# Mikrokrmilnik_RF-detektor.net
KiCad netlist of a schematic drawn in Altium Designer
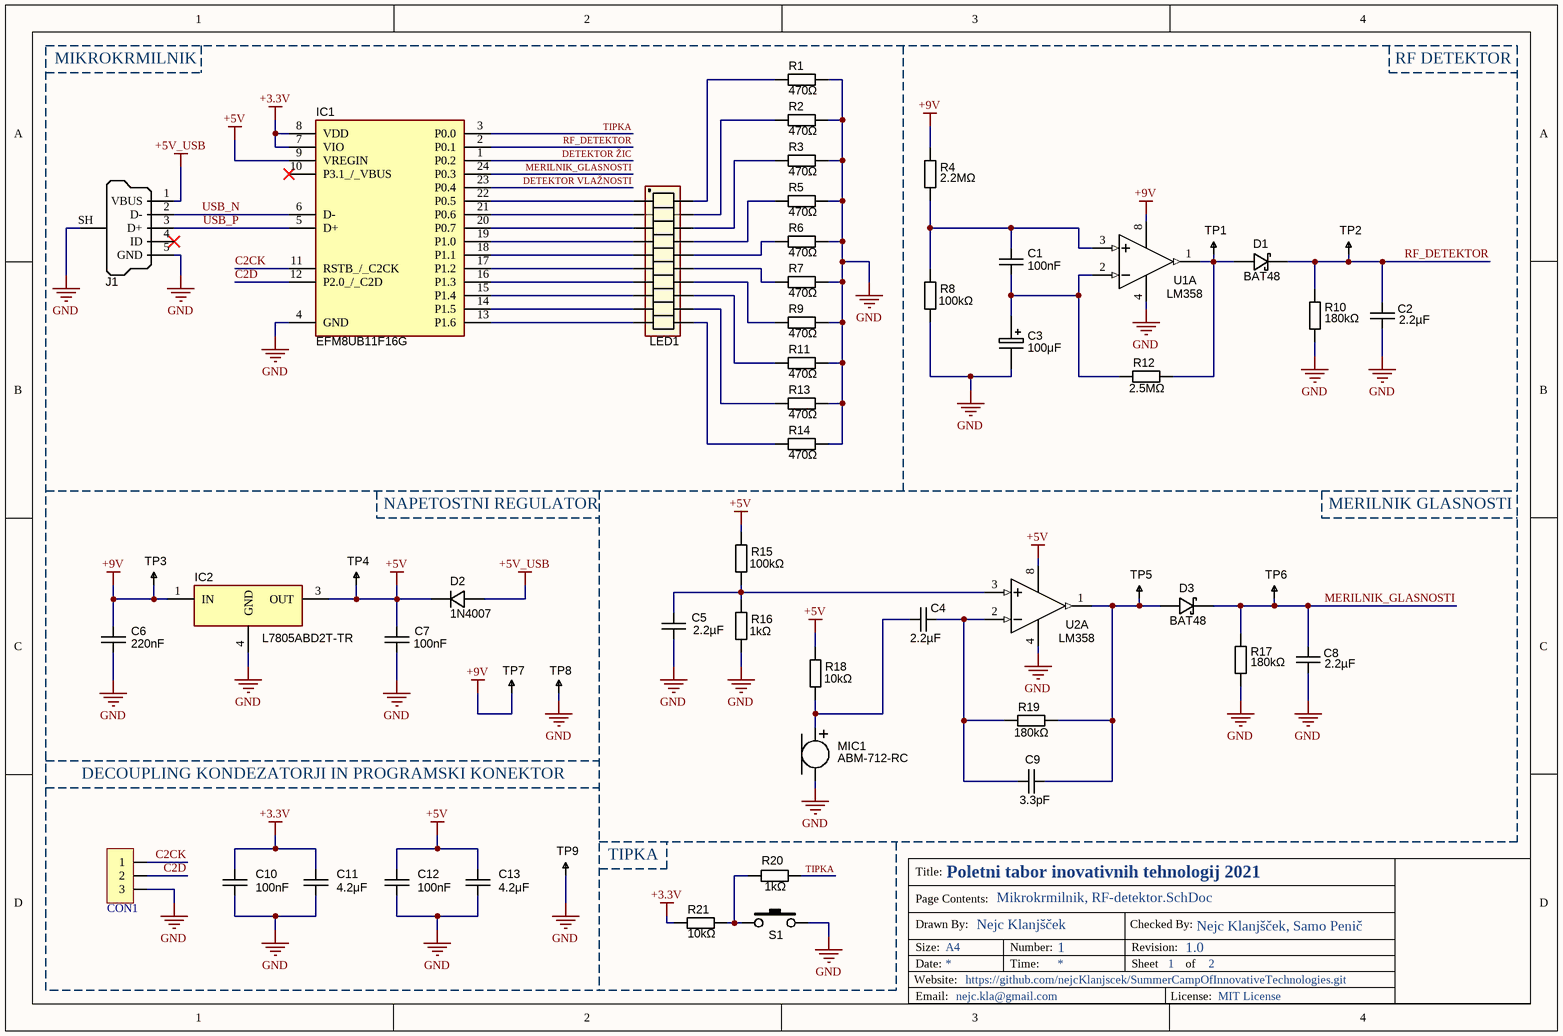
[diagram p0: Mikrokrmilnik, RF-detektor.SchDoc]

(export (version "E")
  (design (tool "Eeschema 10.0.6"))
  (components
    (comp (ref "C1")
      (value "100nF")
      (footprint "B32520C0104J000")
      (description "Capacitor THD Cer 100nF 10% 100V X7R B32520")
      (fields (field (name "TOLERANCE") "±10%") (field (name "Comment") "approved sub OK"))
      (libsource (lib "Nejc Klanjšček") (part "CAPC_220n_B32520"))
    )
    (comp (ref "C2")
      (value "2.2µF")
      (footprint "CAPC500P450250X550")
      (libsource (lib "Nejc Klanjšček") (part "CAPC_2u2_FG28_25V"))
    )
    (comp (ref "C3")
      (value "100μF")
      (footprint "CAPE_5x11x2LS")
      (libsource (lib "Nejc Klanjšček") (part "CAPT_10u_5mm_63V"))
    )
    (comp (ref "C4")
      (value "2.2µF")
      (footprint "CAPC500P450250X550")
      (libsource (lib "Nejc Klanjšček") (part "CAPC_2u2_FG28_25V"))
    )
    (comp (ref "C5")
      (value "2.2µF")
      (footprint "CAPC500P450250X550")
      (libsource (lib "Nejc Klanjšček") (part "CAPC_2u2_FG28_25V"))
    )
    (comp (ref "C6")
      (value "220nF")
      (footprint "CAPC3216N")
      (description "Capacitor SMD Cer 220nF 10% 10V X5R 1206")
      (fields (field (name "TOLERANCE") "±10%") (field (name "Comment") "approved sub OK"))
      (libsource (lib "Nejc Klanjšček") (part "CAPC_10u_1206_10V"))
    )
    (comp (ref "C7")
      (value "100nF")
      (footprint "CAPC3216N")
      (description "Capacitor SMD Cer 100nF 10% 10V X5R 1206")
      (fields (field (name "TOLERANCE") "±10%") (field (name "Comment") "approved sub OK"))
      (libsource (lib "Nejc Klanjšček") (part "CAPC_10u_1206_10V"))
    )
    (comp (ref "C8")
      (value "2.2µF")
      (footprint "CAPC500P450250X550")
      (libsource (lib "Nejc Klanjšček") (part "CAPC_2u2_FG28_25V"))
    )
    (comp (ref "C9")
      (value "3.3pF")
      (footprint "CAPC500P450250X550")
      (libsource (lib "Nejc Klanjšček") (part "CAPC_2u2_FG28_25V"))
    )
    (comp (ref "C10")
      (value "100nF")
      (footprint "CAPC3216N")
      (description "Capacitor SMD Cer 100nF 10% 10V X5R 1206")
      (fields (field (name "TOLERANCE") "±10%") (field (name "Comment") "approved sub OK"))
      (libsource (lib "Nejc Klanjšček") (part "CAPC_10u_1206_10V"))
    )
    (comp (ref "C11")
      (value "4.2μF")
      (footprint "CAPC3216N")
      (description "Capacitor SMD Cer 4.2uF 10% 10V X5R 1206")
      (fields (field (name "TOLERANCE") "±10%") (field (name "Comment") "approved sub OK"))
      (libsource (lib "Nejc Klanjšček") (part "CAPC_10u_1206_10V"))
    )
    (comp (ref "C12")
      (value "100nF")
      (footprint "CAPC3216N")
      (description "Capacitor SMD Cer 100nF 10% 10V X5R 1206")
      (fields (field (name "TOLERANCE") "±10%") (field (name "Comment") "approved sub OK"))
      (libsource (lib "Nejc Klanjšček") (part "CAPC_10u_1206_10V"))
    )
    (comp (ref "C13")
      (value "4.2μF")
      (footprint "CAPC3216N")
      (description "Capacitor SMD Cer 4.2uF 10% 10V X5R 1206")
      (fields (field (name "TOLERANCE") "±10%") (field (name "Comment") "approved sub OK"))
      (libsource (lib "Nejc Klanjšček") (part "CAPC_10u_1206_10V"))
    )
    (comp (ref "CON1")
      (value "H1x3")
      (footprint "H1x3")
      (description "Header 1x8 (male)")
      (libsource (lib "Nejc Klanjšček") (part "H1x3"))
    )
    (comp (ref "D1")
      (value "BAT48")
      (footprint "do-35")
      (description "Diode Schottky SMD 40V 350mA DO-35")
      (libsource (lib "Nejc Klanjšček") (part "DIODE_SCHOTTKY_BAT48"))
    )
    (comp (ref "D2")
      (value "1N4007")
      (footprint "DO-214AC")
      (description "Diode 1N4007 1A 1000V THD")
      (libsource (lib "Nejc Klanjšček") (part "DIODE_1N4007_1000V_1.0A_DO-41"))
    )
    (comp (ref "D3")
      (value "BAT48")
      (footprint "do-35")
      (description "Diode Schottky SMD 40V 350mA DO-35")
      (libsource (lib "Nejc Klanjšček") (part "DIODE_SCHOTTKY_BAT48"))
    )
    (comp (ref "IC1")
      (value "EFM8UB11F16G")
      (footprint "SOP64P600X175-24N")
      (description "Integrated Circuit")
      (fields
        (field (name "MANUFACTURER_PART_NUMBER") "EFM8UB11F16G-C-QSOP24")
        (field (name "MOUSER PART NUMBER") "634-8UB11F16GCQSOP24")
      )
      (libsource (lib "Nejc Klanjšček") (part "EFM8UB11F16G-C-QSOP24"))
    )
    (comp (ref "IC2")
      (value "L7805ABD2T-TR")
      (footprint "D2PAK-STB35NF10T4")
      (description "Integrated Circuit")
      (fields (field (name "MOUSER PART NUMBER") "511-L7805ABD2T-TR"))
      (libsource (lib "Nejc Klanjšček") (part "L7805ABD2T-TR"))
    )
    (comp (ref "J1")
      (value "USB Micro Type B")
      (footprint "USB_Micro-B_FCI_SMD")
      (description "Connector SMD-THD USB Micro Type B middle mount")
      (libsource (lib "Nejc Klanjšček") (part "USB_Micro_TypeB_FCI"))
    )
    (comp (ref "LED1")
      (value "SSA-LXB10HW-GF")
      (footprint "SSA-LXB10HW-GF")
      (libsource (lib "Nejc Klanjšček") (part "SSA-LXB10HW-GF"))
    )
    (comp (ref "MIC1")
      (value "ABM-712-RC")
      (footprint "ABM-707-RC")
      (libsource (lib "Nejc Klanjšček") (part "MICROPHONE_C_ABM-712-RC"))
    )
    (comp (ref "R1")
      (value "470Ω")
      (footprint "RESC3216N")
      (description "Resistor SMD chip 51 Ohm 0.25W 1% 1206")
      (fields (field (name "TOLERANCE") "±1%") (field (name "Comment") "Thick Film"))
      (libsource (lib "Nejc Klanjšček") (part "RES_51R_1206_1%"))
    )
    (comp (ref "R2")
      (value "470Ω")
      (footprint "RESC3216N")
      (description "Resistor SMD chip 51 Ohm 0.25W 1% 1206")
      (fields (field (name "TOLERANCE") "±1%") (field (name "Comment") "Thick Film"))
      (libsource (lib "Nejc Klanjšček") (part "RES_51R_1206_1%"))
    )
    (comp (ref "R3")
      (value "470Ω")
      (footprint "RESC3216N")
      (description "Resistor SMD chip 51 Ohm 0.25W 1% 1206")
      (fields (field (name "TOLERANCE") "±1%") (field (name "Comment") "Thick Film"))
      (libsource (lib "Nejc Klanjšček") (part "RES_51R_1206_1%"))
    )
    (comp (ref "R4")
      (value "2.2MΩ")
      (footprint "RESTH_AXIAL-1/8W")
      (description "Resistor THD Axial 2.2MΩ 0.125W 1% Carbon Film")
      (fields (field (name "TOLERANCE") "±5%") (field (name "Comment") "RES_NL_1/8W"))
      (libsource (lib "Nejc Klanjšček") (part "RES_NL_1/8W"))
    )
    (comp (ref "R5")
      (value "470Ω")
      (footprint "RESC3216N")
      (description "Resistor SMD chip 51 Ohm 0.25W 1% 1206")
      (fields (field (name "TOLERANCE") "±1%") (field (name "Comment") "Thick Film"))
      (libsource (lib "Nejc Klanjšček") (part "RES_51R_1206_1%"))
    )
    (comp (ref "R6")
      (value "470Ω")
      (footprint "RESC3216N")
      (description "Resistor SMD chip 51 Ohm 0.25W 1% 1206")
      (fields (field (name "TOLERANCE") "±1%") (field (name "Comment") "Thick Film"))
      (libsource (lib "Nejc Klanjšček") (part "RES_51R_1206_1%"))
    )
    (comp (ref "R7")
      (value "470Ω")
      (footprint "RESC3216N")
      (description "Resistor SMD chip 51 Ohm 0.25W 1% 1206")
      (fields (field (name "TOLERANCE") "±1%") (field (name "Comment") "Thick Film"))
      (libsource (lib "Nejc Klanjšček") (part "RES_51R_1206_1%"))
    )
    (comp (ref "R8")
      (value "100kΩ")
      (footprint "RESTH_AXIAL-1/8W")
      (description "Resistor THD Axial 100kΩ 0.125W 1% Carbon Film")
      (fields (field (name "TOLERANCE") "±5%") (field (name "Comment") "RES_NL_1/8W"))
      (libsource (lib "Nejc Klanjšček") (part "RES_NL_1/8W"))
    )
    (comp (ref "R9")
      (value "470Ω")
      (footprint "RESC3216N")
      (description "Resistor SMD chip 51 Ohm 0.25W 1% 1206")
      (fields (field (name "TOLERANCE") "±1%") (field (name "Comment") "Thick Film"))
      (libsource (lib "Nejc Klanjšček") (part "RES_51R_1206_1%"))
    )
    (comp (ref "R10")
      (value "180kΩ")
      (footprint "RESTH_AXIAL-1/8W")
      (description "Resistor THD Axial 180kΩ 0.125W 1% Carbon Film")
      (fields (field (name "TOLERANCE") "±5%") (field (name "Comment") "RES_NL_1/8W"))
      (libsource (lib "") (part "RES_NL_1/8W_1"))
    )
    (comp (ref "R11")
      (value "470Ω")
      (footprint "RESC3216N")
      (description "Resistor SMD chip 51 Ohm 0.25W 1% 1206")
      (fields (field (name "TOLERANCE") "±1%") (field (name "Comment") "Thick Film"))
      (libsource (lib "Nejc Klanjšček") (part "RES_51R_1206_1%"))
    )
    (comp (ref "R12")
      (value "2.5MΩ")
      (footprint "RESTH_AXIAL-1/8W")
      (description "Resistor THD Axial 2.5MΩ 0.125W 1% Carbon Film")
      (fields (field (name "TOLERANCE") "±5%") (field (name "Comment") "RES_NL_1/8W"))
      (libsource (lib "") (part "RES_NL_1/8W_2"))
    )
    (comp (ref "R13")
      (value "470Ω")
      (footprint "RESC3216N")
      (description "Resistor SMD chip 51 Ohm 0.25W 1% 1206")
      (fields (field (name "TOLERANCE") "±1%") (field (name "Comment") "Thick Film"))
      (libsource (lib "Nejc Klanjšček") (part "RES_51R_1206_1%"))
    )
    (comp (ref "R14")
      (value "470Ω")
      (footprint "RESC3216N")
      (description "Resistor SMD chip 51 Ohm 0.25W 1% 1206")
      (fields (field (name "TOLERANCE") "±1%") (field (name "Comment") "Thick Film"))
      (libsource (lib "Nejc Klanjšček") (part "RES_51R_1206_1%"))
    )
    (comp (ref "R15")
      (value "100kΩ")
      (footprint "RESTH_AXIAL-1/8W")
      (description "Resistor THD Axial 100kΩ 0.125W 1% Carbon Film")
      (fields (field (name "TOLERANCE") "±5%") (field (name "Comment") "RES_NL_1/8W"))
      (libsource (lib "Nejc Klanjšček") (part "RES_NL_1/8W"))
    )
    (comp (ref "R16")
      (value "1kΩ")
      (footprint "RESTH_AXIAL-1/8W")
      (description "Resistor THD Axial 1kΩ 0.125W 1% Carbon Film")
      (fields (field (name "TOLERANCE") "±5%") (field (name "Comment") "RES_NL_1/8W"))
      (libsource (lib "Nejc Klanjšček") (part "RES_NL_1/8W"))
    )
    (comp (ref "R17")
      (value "180kΩ")
      (footprint "RESTH_AXIAL-1/8W")
      (description "Resistor THD Axial 180kΩ 0.125W 1% Carbon Film")
      (fields (field (name "TOLERANCE") "±5%") (field (name "Comment") "RES_NL_1/8W"))
      (libsource (lib "") (part "RES_NL_1/8W_1"))
    )
    (comp (ref "R18")
      (value "10kΩ")
      (footprint "RESTH_AXIAL-1/8W")
      (description "Resistor THD Axial 1kΩ 0.125W 1% Carbon Film")
      (fields (field (name "TOLERANCE") "±5%") (field (name "Comment") "RES_NL_1/8W"))
      (libsource (lib "Nejc Klanjšček") (part "RES_NL_1/8W"))
    )
    (comp (ref "R19")
      (value "180kΩ")
      (footprint "RESTH_AXIAL-1/8W")
      (description "Resistor THD Axial 180kΩ 0.125W 1% Carbon Film")
      (fields (field (name "TOLERANCE") "±5%") (field (name "Comment") "RES_NL_1/8W"))
      (libsource (lib "") (part "RES_NL_1/8W_3"))
    )
    (comp (ref "R20")
      (value "1kΩ")
      (footprint "RESC3216N")
      (description "Resistor SMD chip 1k Ohm 0.25W 1% 1206")
      (fields (field (name "TOLERANCE") "±1%") (field (name "Comment") "Thick Film"))
      (libsource (lib "Nejc Klanjšček") (part "RES_51R_1206_1%"))
    )
    (comp (ref "R21")
      (value "10kΩ")
      (footprint "RESC3216N")
      (description "Resistor SMD chip 10k Ohm 0.25W 1% 1206")
      (fields (field (name "TOLERANCE") "±1%") (field (name "Comment") "Thick Film"))
      (libsource (lib "") (part "RES_51R_1206_1%_1"))
    )
    (comp (ref "S1")
      (value "SW_THT_PB_7.0mm")
      (footprint "TACT-SWITCH-TS1170")
      (description "Switch, tact, 7.0mm stem")
      (libsource (lib "Nejc Klanjšček") (part "SW_THT_PB_7.0mm"))
    )
    (comp (ref "TP1")
      (value "TESTPOINT")
      (footprint "TP-R60")
      (description "SMD test pin")
      (libsource (lib "Nejc Klanjšček") (part "TESTPOINT"))
    )
    (comp (ref "TP2")
      (value "TESTPOINT")
      (footprint "TP-R60")
      (description "SMD test pin")
      (libsource (lib "Nejc Klanjšček") (part "TESTPOINT"))
    )
    (comp (ref "TP3")
      (value "TESTPOINT")
      (footprint "TP-R60")
      (description "SMD test pin")
      (libsource (lib "Nejc Klanjšček") (part "TESTPOINT"))
    )
    (comp (ref "TP4")
      (value "TESTPOINT")
      (footprint "TP-R60")
      (description "SMD test pin")
      (libsource (lib "Nejc Klanjšček") (part "TESTPOINT"))
    )
    (comp (ref "TP5")
      (value "TESTPOINT")
      (footprint "TP-R60")
      (description "SMD test pin")
      (libsource (lib "Nejc Klanjšček") (part "TESTPOINT"))
    )
    (comp (ref "TP6")
      (value "TESTPOINT")
      (footprint "TP-R60")
      (description "SMD test pin")
      (libsource (lib "Nejc Klanjšček") (part "TESTPOINT"))
    )
    (comp (ref "TP7")
      (value "TESTPOINT_THT")
      (footprint "TP-THT-MULTI")
      (description "Test Point PCB mount Multi-purpose Yellow")
      (libsource (lib "Nejc Klanjšček") (part "TESTPOINT_THT"))
    )
    (comp (ref "TP8")
      (value "TESTPOINT_THT")
      (footprint "TP-THT-MULTI")
      (description "Test Point PCB mount Multi-purpose Yellow")
      (libsource (lib "Nejc Klanjšček") (part "TESTPOINT_THT"))
    )
    (comp (ref "TP9")
      (value "TESTPOINT")
      (footprint "TP-R60")
      (description "SMD test pin")
      (libsource (lib "Nejc Klanjšček") (part "TESTPOINT"))
    )
    (comp (ref "U1")
      (value "LM358")
      (footprint "DIP8-300")
      (description "IC THD Op Amp Precision Micropower SOIC-8")
      (libsource (lib "Nejc Klanjšček") (part "IC_Op-Amp_LM358"))
    )
    (comp (ref "U2")
      (value "LM358")
      (footprint "DIP8-300")
      (description "IC THD Op Amp Precision Micropower SOIC-8")
      (libsource (lib "Nejc Klanjšček") (part "IC_Op-Amp_LM358"))
    )
  )
  (nets
    (net (code "1") (name "+3.3V") (class "Default")
      (node (ref "C10") (pin "1") (pintype "passive"))
      (node (ref "C11") (pin "1") (pintype "passive"))
      (node (ref "IC1") (pin "7") (pinfunction "VIO_7") (pintype "passive"))
      (node (ref "IC1") (pin "8") (pinfunction "VDD_8") (pintype "passive"))
      (node (ref "R21") (pin "1") (pinfunction "1_1") (pintype "passive"))
    )
    (net (code "2") (name "+5V") (class "Default")
      (node (ref "C12") (pin "1") (pintype "passive"))
      (node (ref "C13") (pin "1") (pintype "passive"))
      (node (ref "C7") (pin "1") (pintype "passive"))
      (node (ref "D2") (pin "K") (pinfunction "K_K") (pintype "passive"))
      (node (ref "IC1") (pin "9") (pinfunction "VREGIN_9") (pintype "passive"))
      (node (ref "IC2") (pin "3") (pinfunction "OUT_3") (pintype "passive"))
      (node (ref "R15") (pin "1") (pinfunction "1_1") (pintype "passive"))
      (node (ref "R18") (pin "1") (pinfunction "1_1") (pintype "passive"))
      (node (ref "TP4") (pin "1") (pintype "passive"))
      (node (ref "U2") (pin "8") (pinfunction "V+_8") (pintype "power_in"))
    )
    (net (code "3") (name "+5V_USB") (class "Default")
      (node (ref "D2") (pin "A") (pinfunction "A_A") (pintype "passive"))
      (node (ref "J1") (pin "1") (pinfunction "VBUS_1") (pintype "passive"))
    )
    (net (code "4") (name "+9V") (class "Default")
      (node (ref "C6") (pin "1") (pintype "passive"))
      (node (ref "IC2") (pin "1") (pinfunction "IN_1") (pintype "passive"))
      (node (ref "R4") (pin "1") (pinfunction "1_1") (pintype "passive"))
      (node (ref "TP3") (pin "1") (pintype "passive"))
      (node (ref "TP7") (pin "1") (pintype "passive"))
      (node (ref "U1") (pin "8") (pinfunction "V+_8") (pintype "power_in"))
    )
    (net (code "5") (name "/C2CK") (class "Default")
      (node (ref "CON1") (pin "1") (pinfunction "1_1") (pintype "passive"))
      (node (ref "IC1") (pin "11") (pinfunction "RSTB_/_C2CK_11") (pintype "passive"))
    )
    (net (code "6") (name "/C2D") (class "Default")
      (node (ref "CON1") (pin "2") (pinfunction "2_2") (pintype "passive"))
      (node (ref "IC1") (pin "12") (pinfunction "P2.0_/_C2D_12") (pintype "passive"))
    )
    (net (code "7") (name "/DETEKTOR VLAŽNOSTI") (class "Default")
      (node (ref "IC1") (pin "23") (pinfunction "P0.4_23") (pintype "passive"))
    )
    (net (code "8") (name "/DETEKTOR ŽIC") (class "Default")
      (node (ref "IC1") (pin "1") (pinfunction "P0.2_1") (pintype "passive"))
    )
    (net (code "9") (name "/MERILNIK_GLASNOSTI") (class "Default")
      (node (ref "C8") (pin "1") (pintype "passive"))
      (node (ref "D3") (pin "K") (pinfunction "K_K") (pintype "passive"))
      (node (ref "IC1") (pin "24") (pinfunction "P0.3_24") (pintype "passive"))
      (node (ref "R17") (pin "2") (pinfunction "2_2") (pintype "passive"))
      (node (ref "TP6") (pin "1") (pintype "passive"))
    )
    (net (code "10") (name "/RF_DETEKTOR") (class "Default")
      (node (ref "C2") (pin "1") (pintype "passive"))
      (node (ref "D1") (pin "K") (pinfunction "K_K") (pintype "passive"))
      (node (ref "IC1") (pin "2") (pinfunction "P0.1_2") (pintype "passive"))
      (node (ref "R10") (pin "2") (pinfunction "2_2") (pintype "passive"))
      (node (ref "TP2") (pin "1") (pintype "passive"))
    )
    (net (code "11") (name "/TIPKA") (class "Default")
      (node (ref "IC1") (pin "3") (pinfunction "P0.0_3") (pintype "passive"))
      (node (ref "R20") (pin "1") (pinfunction "1_1") (pintype "passive"))
    )
    (net (code "12") (name "/USB_N") (class "Default")
      (node (ref "IC1") (pin "6") (pinfunction "D-_6") (pintype "passive"))
      (node (ref "J1") (pin "2") (pinfunction "D-_2") (pintype "passive"))
    )
    (net (code "13") (name "/USB_P") (class "Default")
      (node (ref "IC1") (pin "5") (pinfunction "D+_5") (pintype "passive"))
      (node (ref "J1") (pin "3") (pinfunction "D+_3") (pintype "passive"))
    )
    (net (code "14") (name "GND") (class "Default")
      (node (ref "C10") (pin "2") (pintype "passive"))
      (node (ref "C11") (pin "2") (pintype "passive"))
      (node (ref "C12") (pin "2") (pintype "passive"))
      (node (ref "C13") (pin "2") (pintype "passive"))
      (node (ref "C2") (pin "2") (pintype "passive"))
      (node (ref "C3") (pin "2") (pintype "passive"))
      (node (ref "C5") (pin "1") (pintype "passive"))
      (node (ref "C6") (pin "2") (pintype "passive"))
      (node (ref "C7") (pin "2") (pintype "passive"))
      (node (ref "C8") (pin "2") (pintype "passive"))
      (node (ref "CON1") (pin "3") (pinfunction "3_3") (pintype "passive"))
      (node (ref "IC1") (pin "4") (pinfunction "GND_4") (pintype "passive"))
      (node (ref "IC2") (pin "4") (pinfunction "GND_4") (pintype "passive"))
      (node (ref "J1") (pin "5") (pinfunction "GND_5") (pintype "passive"))
      (node (ref "J1") (pin "SH") (pinfunction "Shell_SH") (pintype "passive"))
      (node (ref "MIC1") (pin "2") (pinfunction "-_2") (pintype "passive"))
      (node (ref "R1") (pin "1") (pinfunction "1_1") (pintype "passive"))
      (node (ref "R10") (pin "1") (pinfunction "1_1") (pintype "passive"))
      (node (ref "R11") (pin "1") (pinfunction "1_1") (pintype "passive"))
      (node (ref "R13") (pin "1") (pinfunction "1_1") (pintype "passive"))
      (node (ref "R14") (pin "1") (pinfunction "1_1") (pintype "passive"))
      (node (ref "R16") (pin "2") (pinfunction "2_2") (pintype "passive"))
      (node (ref "R17") (pin "1") (pinfunction "1_1") (pintype "passive"))
      (node (ref "R2") (pin "1") (pinfunction "1_1") (pintype "passive"))
      (node (ref "R3") (pin "1") (pinfunction "1_1") (pintype "passive"))
      (node (ref "R5") (pin "1") (pinfunction "1_1") (pintype "passive"))
      (node (ref "R6") (pin "1") (pinfunction "1_1") (pintype "passive"))
      (node (ref "R7") (pin "1") (pinfunction "1_1") (pintype "passive"))
      (node (ref "R8") (pin "2") (pinfunction "2_2") (pintype "passive"))
      (node (ref "R9") (pin "1") (pinfunction "1_1") (pintype "passive"))
      (node (ref "S1") (pin "2") (pintype "passive"))
      (node (ref "TP8") (pin "1") (pintype "passive"))
      (node (ref "TP9") (pin "1") (pintype "passive"))
      (node (ref "U1") (pin "4") (pinfunction "V-_4") (pintype "power_in"))
      (node (ref "U2") (pin "4") (pinfunction "V-_4") (pintype "power_in"))
    )
    (net (code "15") (name "Net-(IC1-P0.5)") (class "Default")
      (node (ref "IC1") (pin "22") (pinfunction "P0.5_22") (pintype "passive"))
      (node (ref "LED1") (pin "1") (pinfunction "1_1") (pintype "passive"))
    )
    (net (code "16") (name "Net-(IC1-P0.6)") (class "Default")
      (node (ref "IC1") (pin "21") (pinfunction "P0.6_21") (pintype "passive"))
      (node (ref "LED1") (pin "2") (pinfunction "2_2") (pintype "passive"))
    )
    (net (code "17") (name "Net-(IC1-P0.7)") (class "Default")
      (node (ref "IC1") (pin "20") (pinfunction "P0.7_20") (pintype "passive"))
      (node (ref "LED1") (pin "3") (pinfunction "3_3") (pintype "passive"))
    )
    (net (code "18") (name "Net-(IC1-P1.0)") (class "Default")
      (node (ref "IC1") (pin "19") (pinfunction "P1.0_19") (pintype "passive"))
      (node (ref "LED1") (pin "4") (pinfunction "4_4") (pintype "passive"))
    )
    (net (code "19") (name "Net-(IC1-P1.1)") (class "Default")
      (node (ref "IC1") (pin "18") (pinfunction "P1.1_18") (pintype "passive"))
      (node (ref "LED1") (pin "5") (pinfunction "5_5") (pintype "passive"))
    )
    (net (code "20") (name "Net-(IC1-P1.2)") (class "Default")
      (node (ref "IC1") (pin "17") (pinfunction "P1.2_17") (pintype "passive"))
      (node (ref "LED1") (pin "6") (pinfunction "6_6") (pintype "passive"))
    )
    (net (code "21") (name "Net-(IC1-P1.3)") (class "Default")
      (node (ref "IC1") (pin "16") (pinfunction "P1.3_16") (pintype "passive"))
      (node (ref "LED1") (pin "7") (pinfunction "7_7") (pintype "passive"))
    )
    (net (code "22") (name "Net-(IC1-P1.4)") (class "Default")
      (node (ref "IC1") (pin "15") (pinfunction "P1.4_15") (pintype "passive"))
      (node (ref "LED1") (pin "8") (pinfunction "8_8") (pintype "passive"))
    )
    (net (code "23") (name "Net-(IC1-P1.5)") (class "Default")
      (node (ref "IC1") (pin "14") (pinfunction "P1.5_14") (pintype "passive"))
      (node (ref "LED1") (pin "9") (pinfunction "9_9") (pintype "passive"))
    )
    (net (code "24") (name "Net-(IC1-P1.6)") (class "Default")
      (node (ref "IC1") (pin "13") (pinfunction "P1.6_13") (pintype "passive"))
      (node (ref "LED1") (pin "10") (pinfunction "10_10") (pintype "passive"))
    )
    (net (code "25") (name "Net-(LED1-Pad11)") (class "Default")
      (node (ref "LED1") (pin "11") (pinfunction "11_11") (pintype "passive"))
      (node (ref "R14") (pin "2") (pinfunction "2_2") (pintype "passive"))
    )
    (net (code "26") (name "Net-(LED1-Pad12)") (class "Default")
      (node (ref "LED1") (pin "12") (pinfunction "12_12") (pintype "passive"))
      (node (ref "R13") (pin "2") (pinfunction "2_2") (pintype "passive"))
    )
    (net (code "27") (name "Net-(LED1-Pad13)") (class "Default")
      (node (ref "LED1") (pin "13") (pinfunction "13_13") (pintype "passive"))
      (node (ref "R11") (pin "2") (pinfunction "2_2") (pintype "passive"))
    )
    (net (code "28") (name "Net-(LED1-Pad14)") (class "Default")
      (node (ref "LED1") (pin "14") (pinfunction "14_14") (pintype "passive"))
      (node (ref "R9") (pin "2") (pinfunction "2_2") (pintype "passive"))
    )
    (net (code "29") (name "Net-(LED1-Pad15)") (class "Default")
      (node (ref "LED1") (pin "15") (pinfunction "15_15") (pintype "passive"))
      (node (ref "R7") (pin "2") (pinfunction "2_2") (pintype "passive"))
    )
    (net (code "30") (name "Net-(LED1-Pad16)") (class "Default")
      (node (ref "LED1") (pin "16") (pinfunction "16_16") (pintype "passive"))
      (node (ref "R6") (pin "2") (pinfunction "2_2") (pintype "passive"))
    )
    (net (code "31") (name "Net-(LED1-Pad17)") (class "Default")
      (node (ref "LED1") (pin "17") (pinfunction "17_17") (pintype "passive"))
      (node (ref "R5") (pin "2") (pinfunction "2_2") (pintype "passive"))
    )
    (net (code "32") (name "Net-(LED1-Pad18)") (class "Default")
      (node (ref "LED1") (pin "18") (pinfunction "18_18") (pintype "passive"))
      (node (ref "R3") (pin "2") (pinfunction "2_2") (pintype "passive"))
    )
    (net (code "33") (name "Net-(LED1-Pad19)") (class "Default")
      (node (ref "LED1") (pin "19") (pinfunction "19_19") (pintype "passive"))
      (node (ref "R2") (pin "2") (pinfunction "2_2") (pintype "passive"))
    )
    (net (code "34") (name "Net-(LED1-Pad20)") (class "Default")
      (node (ref "LED1") (pin "20") (pinfunction "20_20") (pintype "passive"))
      (node (ref "R1") (pin "2") (pinfunction "2_2") (pintype "passive"))
    )
    (net (code "35") (name "Net-(MIC1-+)") (class "Default")
      (node (ref "C4") (pin "1") (pintype "passive"))
      (node (ref "MIC1") (pin "1") (pinfunction "+_1") (pintype "passive"))
      (node (ref "R18") (pin "2") (pinfunction "2_2") (pintype "passive"))
    )
    (net (code "36") (name "Net-(R20-Pad2)") (class "Default")
      (node (ref "R20") (pin "2") (pinfunction "2_2") (pintype "passive"))
      (node (ref "R21") (pin "2") (pinfunction "2_2") (pintype "passive"))
      (node (ref "S1") (pin "1") (pintype "passive"))
    )
    (net (code "37") (name "Net-(U1A-IN+)") (class "Default")
      (node (ref "C1") (pin "1") (pintype "passive"))
      (node (ref "R4") (pin "2") (pinfunction "2_2") (pintype "passive"))
      (node (ref "R8") (pin "1") (pinfunction "1_1") (pintype "passive"))
      (node (ref "U1") (pin "3") (pinfunction "IN+_3") (pintype "input"))
    )
    (net (code "38") (name "Net-(U1A-IN-)") (class "Default")
      (node (ref "C1") (pin "2") (pintype "passive"))
      (node (ref "C3") (pin "1") (pintype "passive"))
      (node (ref "R12") (pin "1") (pinfunction "1_1") (pintype "passive"))
      (node (ref "U1") (pin "2") (pinfunction "IN-_2") (pintype "input"))
    )
    (net (code "39") (name "Net-(U1A-OUT)") (class "Default")
      (node (ref "D1") (pin "A") (pinfunction "A_A") (pintype "passive"))
      (node (ref "R12") (pin "2") (pinfunction "2_2") (pintype "passive"))
      (node (ref "TP1") (pin "1") (pintype "passive"))
      (node (ref "U1") (pin "1") (pinfunction "OUT_1") (pintype "output"))
    )
    (net (code "40") (name "Net-(U2A-IN+)") (class "Default")
      (node (ref "C5") (pin "2") (pintype "passive"))
      (node (ref "R15") (pin "2") (pinfunction "2_2") (pintype "passive"))
      (node (ref "R16") (pin "1") (pinfunction "1_1") (pintype "passive"))
      (node (ref "U2") (pin "3") (pinfunction "IN+_3") (pintype "input"))
    )
    (net (code "41") (name "Net-(U2A-IN-)") (class "Default")
      (node (ref "C4") (pin "2") (pintype "passive"))
      (node (ref "C9") (pin "1") (pintype "passive"))
      (node (ref "R19") (pin "2") (pinfunction "2_2") (pintype "passive"))
      (node (ref "U2") (pin "2") (pinfunction "IN-_2") (pintype "input"))
    )
    (net (code "42") (name "Net-(U2A-OUT)") (class "Default")
      (node (ref "C9") (pin "2") (pintype "passive"))
      (node (ref "D3") (pin "A") (pinfunction "A_A") (pintype "passive"))
      (node (ref "R19") (pin "1") (pinfunction "1_1") (pintype "passive"))
      (node (ref "TP5") (pin "1") (pintype "passive"))
      (node (ref "U2") (pin "1") (pinfunction "OUT_1") (pintype "output"))
    )
    (net (code "43") (name "unconnected-(IC1-P3.1_{slash}_VBUS-Pad10)") (class "Default")
      (node (ref "IC1") (pin "10") (pinfunction "P3.1_/_VBUS_10") (pintype "passive+no_connect"))
    )
    (net (code "44") (name "unconnected-(J1-ID-Pad4)") (class "Default")
      (node (ref "J1") (pin "4") (pinfunction "ID_4") (pintype "passive+no_connect"))
    )
  )
)
